# RPi_RFM12B_ISP.net
KiCad netlist of a schematic drawn in EAGLE
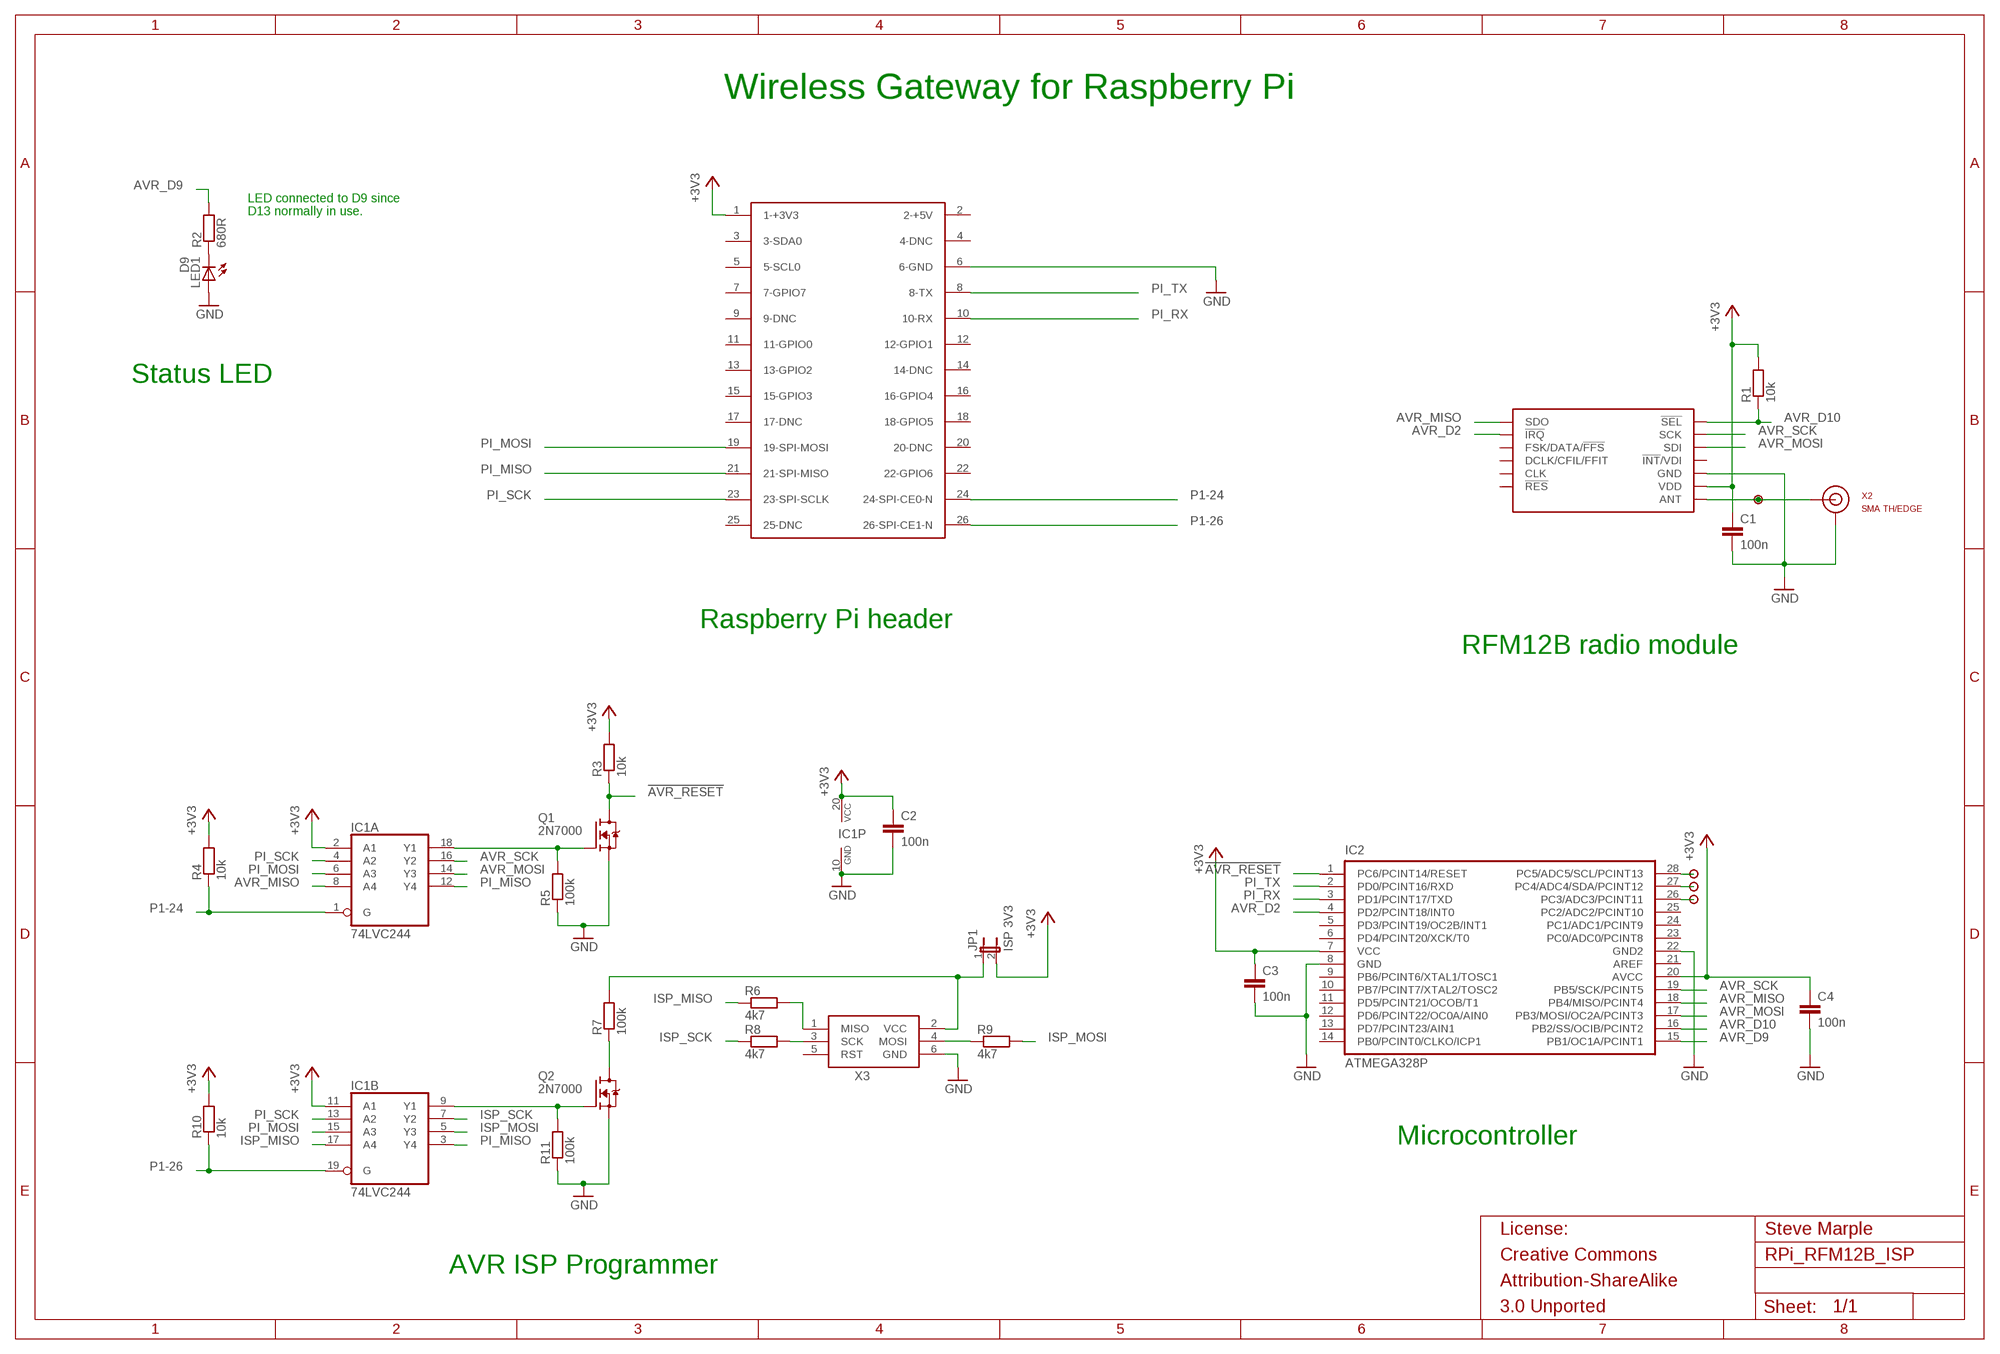
[diagram p0: schematic, sheet 1]

(export (version "E")
  (design (tool "Eeschema 10.0.6"))
  (components
    (comp (ref "AVR_A1")
      (value "PAD")
      (footprint "eagle-import:PAD")
      (libsource (lib "eagle-import") (part "PAD"))
    )
    (comp (ref "AVR_A2")
      (value "PAD")
      (footprint "eagle-import:PAD")
      (libsource (lib "eagle-import") (part "PAD"))
    )
    (comp (ref "AVR_A3")
      (value "PAD")
      (footprint "eagle-import:PAD")
      (libsource (lib "eagle-import") (part "PAD"))
    )
    (comp (ref "C1")
      (value "100n")
      (footprint "eagle-import:CAP-PTH-SMALL")
      (libsource (lib "eagle-import") (part "CAPPTH"))
    )
    (comp (ref "C2")
      (value "100n")
      (footprint "eagle-import:CAP-PTH-SMALL")
      (libsource (lib "eagle-import") (part "CAPPTH"))
    )
    (comp (ref "C3")
      (value "100n")
      (footprint "eagle-import:CAP-PTH-SMALL")
      (libsource (lib "eagle-import") (part "CAPPTH"))
    )
    (comp (ref "C4")
      (value "100n")
      (footprint "eagle-import:CAP-PTH-SMALL")
      (libsource (lib "eagle-import") (part "CAPPTH"))
    )
    (comp (ref "IC1")
      (value "74LVC244")
      (footprint "eagle-import:DIL20")
      (libsource (lib "eagle-import") (part "74244NHC"))
    )
    (comp (ref "IC2")
      (value "ATMEGA328P")
      (footprint "eagle-import:DIL28-N")
      (libsource (lib "eagle-import") (part "IC_UC_ATMEGA328PDIL"))
    )
    (comp (ref "JP1")
      (value "ISP 3V3")
      (footprint "eagle-import:1X02")
      (libsource (lib "eagle-import") (part "JUMPER-2PTH"))
    )
    (comp (ref "LED1")
      (value "D9")
      (footprint "eagle-import:LED3MM")
      (libsource (lib "eagle-import") (part "LED3MM"))
    )
    (comp (ref "Q1")
      (value "2N7000")
      (footprint "eagle-import:TO-92")
      (libsource (lib "eagle-import") (part "2N7000"))
    )
    (comp (ref "Q2")
      (value "2N7000")
      (footprint "eagle-import:TO-92")
      (libsource (lib "eagle-import") (part "2N7000"))
    )
    (comp (ref "R1")
      (value "10k")
      (footprint "eagle-import:RES-AXIAL-0.4")
      (libsource (lib "eagle-import") (part "RESISTOR"))
    )
    (comp (ref "R2")
      (value "680R")
      (footprint "eagle-import:RES-AXIAL-0.4")
      (libsource (lib "eagle-import") (part "RESISTOR"))
    )
    (comp (ref "R3")
      (value "10k")
      (footprint "eagle-import:RES-AXIAL-0.4")
      (libsource (lib "eagle-import") (part "RESISTOR"))
    )
    (comp (ref "R4")
      (value "10k")
      (footprint "eagle-import:RES-AXIAL-0.4")
      (libsource (lib "eagle-import") (part "RESISTOR"))
    )
    (comp (ref "R5")
      (value "100k")
      (footprint "eagle-import:RES-AXIAL-0.4")
      (libsource (lib "eagle-import") (part "RESISTOR"))
    )
    (comp (ref "R6")
      (value "4k7")
      (footprint "eagle-import:RES-AXIAL-0.4")
      (libsource (lib "eagle-import") (part "RESISTOR"))
    )
    (comp (ref "R7")
      (value "100k")
      (footprint "eagle-import:RES-AXIAL-0.4")
      (libsource (lib "eagle-import") (part "RESISTOR"))
    )
    (comp (ref "R8")
      (value "4k7")
      (footprint "eagle-import:RES-AXIAL-0.4")
      (libsource (lib "eagle-import") (part "RESISTOR"))
    )
    (comp (ref "R9")
      (value "4k7")
      (footprint "eagle-import:RES-AXIAL-0.4")
      (libsource (lib "eagle-import") (part "RESISTOR"))
    )
    (comp (ref "R10")
      (value "10k")
      (footprint "eagle-import:RES-AXIAL-0.4")
      (libsource (lib "eagle-import") (part "RESISTOR"))
    )
    (comp (ref "R11")
      (value "100k")
      (footprint "eagle-import:RES-AXIAL-0.4")
      (libsource (lib "eagle-import") (part "RESISTOR"))
    )
    (comp (ref "RF1")
      (value "RFM12B")
      (footprint "eagle-import:RFM12B")
      (libsource (lib "eagle-import") (part "RFM12BSMD"))
    )
    (comp (ref "RFM12B_ANT")
      (value "PAD")
      (footprint "eagle-import:PAD")
      (libsource (lib "eagle-import") (part "PAD"))
    )
    (comp (ref "X1")
      (value "P1A")
      (footprint "eagle-import:RASPBERRY-PI-HEADER")
      (libsource (lib "eagle-import") (part "RASPBERRY-PIHEADER"))
    )
    (comp (ref "X2")
      (value "SMA TH/EDGE")
      (footprint "eagle-import:SMA-THD-EDGE")
      (libsource (lib "eagle-import") (part "CONN-SMATHD-SMD-EDGE"))
    )
    (comp (ref "X3")
      (value "AVR ISP")
      (footprint "eagle-import:CONN-HARTING-ML6")
      (libsource (lib "eagle-import") (part "AVRISP-HEADER-6-SHROUDED"))
    )
  )
  (nets
    (net (code "1") (name "+3V3") (class "Default")
      (node (ref "C1") (pin "1") (pinfunction "1_1") (pintype "passive"))
      (node (ref "C2") (pin "1") (pinfunction "1_1") (pintype "passive"))
      (node (ref "C3") (pin "1") (pinfunction "1_1") (pintype "passive"))
      (node (ref "C4") (pin "1") (pinfunction "1_1") (pintype "passive"))
      (node (ref "IC1") (pin "11") (pinfunction "A1_11") (pintype "input"))
      (node (ref "IC1") (pin "2") (pinfunction "A1_2") (pintype "input"))
      (node (ref "IC1") (pin "20") (pinfunction "VCC_20") (pintype "power_in"))
      (node (ref "IC2") (pin "20") (pinfunction "AVCC_20") (pintype "bidirectional"))
      (node (ref "IC2") (pin "7") (pinfunction "VCC_7") (pintype "bidirectional"))
      (node (ref "JP1") (pin "2") (pinfunction "2_2") (pintype "passive"))
      (node (ref "R1") (pin "P$2") (pinfunction "2_P$2") (pintype "passive"))
      (node (ref "R10") (pin "P$2") (pinfunction "2_P$2") (pintype "passive"))
      (node (ref "R3") (pin "P$2") (pinfunction "2_P$2") (pintype "passive"))
      (node (ref "R4") (pin "P$2") (pinfunction "2_P$2") (pintype "passive"))
      (node (ref "RF1") (pin "VDD") (pinfunction "VDD_VDD") (pintype "power_in"))
      (node (ref "X1") (pin "1") (pinfunction "1-+3V3_1") (pintype "bidirectional"))
    )
    (net (code "2") (name "/AVR_D2") (class "Default")
      (node (ref "IC2") (pin "4") (pinfunction "PD2/PCINT18/INT0_4") (pintype "bidirectional"))
      (node (ref "RF1") (pin "!IRQ") (pinfunction "~{IRQ}_!IRQ") (pintype "output"))
    )
    (net (code "3") (name "/AVR_D9") (class "Default")
      (node (ref "IC2") (pin "15") (pinfunction "PB1/OC1A/PCINT1_15") (pintype "bidirectional"))
      (node (ref "R2") (pin "P$2") (pinfunction "2_P$2") (pintype "passive"))
    )
    (net (code "4") (name "/AVR_D10") (class "Default")
      (node (ref "IC2") (pin "16") (pinfunction "PB2/SS/OCIB/PCINT2_16") (pintype "bidirectional"))
      (node (ref "R1") (pin "P$1") (pinfunction "1_P$1") (pintype "passive"))
      (node (ref "RF1") (pin "!SEL") (pinfunction "~{SEL}_!SEL") (pintype "input"))
    )
    (net (code "5") (name "/AVR_MISO") (class "Default")
      (node (ref "IC1") (pin "8") (pinfunction "A4_8") (pintype "input"))
      (node (ref "IC2") (pin "18") (pinfunction "PB4/MISO/PCINT4_18") (pintype "bidirectional"))
      (node (ref "RF1") (pin "SDO") (pinfunction "SDO_SDO") (pintype "output"))
    )
    (net (code "6") (name "/AVR_MOSI") (class "Default")
      (node (ref "IC1") (pin "14") (pinfunction "Y3_14") (pintype "tri_state"))
      (node (ref "IC2") (pin "17") (pinfunction "PB3/MOSI/OC2A/PCINT3_17") (pintype "bidirectional"))
      (node (ref "RF1") (pin "SDI") (pinfunction "SDI_SDI") (pintype "input"))
    )
    (net (code "7") (name "/AVR_SCK") (class "Default")
      (node (ref "IC1") (pin "16") (pinfunction "Y2_16") (pintype "tri_state"))
      (node (ref "IC2") (pin "19") (pinfunction "PB5/SCK/PCINT5_19") (pintype "bidirectional"))
      (node (ref "RF1") (pin "SCK") (pinfunction "SCK_SCK") (pintype "input"))
    )
    (net (code "8") (name "/ISP_MISO") (class "Default")
      (node (ref "IC1") (pin "17") (pinfunction "A4_17") (pintype "input"))
      (node (ref "R6") (pin "P$1") (pinfunction "1_P$1") (pintype "passive"))
    )
    (net (code "9") (name "/ISP_MOSI") (class "Default")
      (node (ref "IC1") (pin "5") (pinfunction "Y3_5") (pintype "tri_state"))
      (node (ref "R9") (pin "P$2") (pinfunction "2_P$2") (pintype "passive"))
    )
    (net (code "10") (name "/ISP_SCK") (class "Default")
      (node (ref "IC1") (pin "7") (pinfunction "Y2_7") (pintype "tri_state"))
      (node (ref "R8") (pin "P$1") (pinfunction "1_P$1") (pintype "passive"))
    )
    (net (code "11") (name "/P1-24") (class "Default")
      (node (ref "IC1") (pin "1") (pinfunction "G_1") (pintype "input"))
      (node (ref "R4") (pin "P$1") (pinfunction "1_P$1") (pintype "passive"))
      (node (ref "X1") (pin "24") (pinfunction "24-SPI-CE0-N_24") (pintype "bidirectional"))
    )
    (net (code "12") (name "/P1-26") (class "Default")
      (node (ref "IC1") (pin "19") (pinfunction "G_19") (pintype "input"))
      (node (ref "R10") (pin "P$1") (pinfunction "1_P$1") (pintype "passive"))
      (node (ref "X1") (pin "26") (pinfunction "26-SPI-CE1-N_26") (pintype "bidirectional"))
    )
    (net (code "13") (name "/PI_MISO") (class "Default")
      (node (ref "IC1") (pin "12") (pinfunction "Y4_12") (pintype "tri_state"))
      (node (ref "IC1") (pin "3") (pinfunction "Y4_3") (pintype "tri_state"))
      (node (ref "X1") (pin "21") (pinfunction "21-SPI-MISO_21") (pintype "bidirectional"))
    )
    (net (code "14") (name "/PI_MOSI") (class "Default")
      (node (ref "IC1") (pin "15") (pinfunction "A3_15") (pintype "input"))
      (node (ref "IC1") (pin "6") (pinfunction "A3_6") (pintype "input"))
      (node (ref "X1") (pin "19") (pinfunction "19-SPI-MOSI_19") (pintype "bidirectional"))
    )
    (net (code "15") (name "/PI_RX") (class "Default")
      (node (ref "IC2") (pin "3") (pinfunction "PD1/PCINT17/TXD_3") (pintype "bidirectional"))
      (node (ref "X1") (pin "10") (pinfunction "10-RX_10") (pintype "bidirectional"))
    )
    (net (code "16") (name "/PI_SCK") (class "Default")
      (node (ref "IC1") (pin "13") (pinfunction "A2_13") (pintype "input"))
      (node (ref "IC1") (pin "4") (pinfunction "A2_4") (pintype "input"))
      (node (ref "X1") (pin "23") (pinfunction "23-SPI-SCLK_23") (pintype "bidirectional"))
    )
    (net (code "17") (name "/PI_TX") (class "Default")
      (node (ref "IC2") (pin "2") (pinfunction "PD0/PCINT16/RXD_2") (pintype "bidirectional"))
      (node (ref "X1") (pin "8") (pinfunction "8-TX_8") (pintype "bidirectional"))
    )
    (net (code "18") (name "/~{AVR_RESET}") (class "Default")
      (node (ref "IC2") (pin "1") (pinfunction "PC6/PCINT14/RESET_1") (pintype "bidirectional"))
      (node (ref "Q1") (pin "3") (pinfunction "D_3") (pintype "passive"))
      (node (ref "R3") (pin "P$1") (pinfunction "1_P$1") (pintype "passive"))
    )
    (net (code "19") (name "GND") (class "Default")
      (node (ref "C1") (pin "2") (pinfunction "2_2") (pintype "passive"))
      (node (ref "C2") (pin "2") (pinfunction "2_2") (pintype "passive"))
      (node (ref "C3") (pin "2") (pinfunction "2_2") (pintype "passive"))
      (node (ref "C4") (pin "2") (pinfunction "2_2") (pintype "passive"))
      (node (ref "IC1") (pin "10") (pinfunction "GND_10") (pintype "power_in"))
      (node (ref "IC2") (pin "22") (pinfunction "GND2_22") (pintype "bidirectional"))
      (node (ref "IC2") (pin "8") (pinfunction "GND_8") (pintype "bidirectional"))
      (node (ref "LED1") (pin "A") (pinfunction "A_A") (pintype "passive"))
      (node (ref "Q1") (pin "1") (pinfunction "S_1") (pintype "passive"))
      (node (ref "Q2") (pin "1") (pinfunction "S_1") (pintype "passive"))
      (node (ref "R11") (pin "P$1") (pinfunction "1_P$1") (pintype "passive"))
      (node (ref "R5") (pin "P$1") (pinfunction "1_P$1") (pintype "passive"))
      (node (ref "RF1") (pin "GND@0") (pinfunction "GND_GND@0") (pintype "power_in"))
      (node (ref "RF1") (pin "GND@1") (pinfunction "GND_GND@1") (pintype "power_in"))
      (node (ref "X1") (pin "6") (pinfunction "6-GND_6") (pintype "bidirectional"))
      (node (ref "X2") (pin "GND@0") (pinfunction "GND_GND@0") (pintype "bidirectional"))
      (node (ref "X2") (pin "GND@1") (pinfunction "GND_GND@1") (pintype "bidirectional"))
      (node (ref "X2") (pin "GND@2") (pinfunction "GND_GND@2") (pintype "bidirectional"))
      (node (ref "X2") (pin "GND@3") (pinfunction "GND_GND@3") (pintype "bidirectional"))
      (node (ref "X2") (pin "GND@EDGE0") (pinfunction "GND_GND@EDGE0") (pintype "bidirectional"))
      (node (ref "X2") (pin "GND@EDGE1") (pinfunction "GND_GND@EDGE1") (pintype "bidirectional"))
      (node (ref "X2") (pin "GND@EDGE2") (pinfunction "GND_GND@EDGE2") (pintype "bidirectional"))
      (node (ref "X2") (pin "GND@EDGE3") (pinfunction "GND_GND@EDGE3") (pintype "bidirectional"))
      (node (ref "X3") (pin "6") (pinfunction "GND_6") (pintype "power_in"))
    )
    (net (code "20") (name "Net-(IC1A-Y1)") (class "Default")
      (node (ref "IC1") (pin "18") (pinfunction "Y1_18") (pintype "tri_state"))
      (node (ref "Q1") (pin "2") (pinfunction "G_2") (pintype "passive"))
      (node (ref "R5") (pin "P$2") (pinfunction "2_P$2") (pintype "passive"))
    )
    (net (code "21") (name "Net-(IC1B-Y1)") (class "Default")
      (node (ref "IC1") (pin "9") (pinfunction "Y1_9") (pintype "tri_state"))
      (node (ref "Q2") (pin "2") (pinfunction "G_2") (pintype "passive"))
      (node (ref "R11") (pin "P$2") (pinfunction "2_P$2") (pintype "passive"))
    )
    (net (code "22") (name "Net-(IC2-PC3{slash}ADC3{slash}PCINT11)") (class "Default")
      (node (ref "AVR_A3") (pin "1") (pinfunction "1_1") (pintype "bidirectional"))
      (node (ref "IC2") (pin "26") (pinfunction "PC3/ADC3/PCINT11_26") (pintype "bidirectional"))
    )
    (net (code "23") (name "Net-(IC2-PC4{slash}ADC4{slash}SDA{slash}PCINT12)") (class "Default")
      (node (ref "AVR_A2") (pin "1") (pinfunction "1_1") (pintype "bidirectional"))
      (node (ref "IC2") (pin "27") (pinfunction "PC4/ADC4/SDA/PCINT12_27") (pintype "bidirectional"))
    )
    (net (code "24") (name "Net-(IC2-PC5{slash}ADC5{slash}SCL{slash}PCINT13)") (class "Default")
      (node (ref "AVR_A1") (pin "1") (pinfunction "1_1") (pintype "bidirectional"))
      (node (ref "IC2") (pin "28") (pinfunction "PC5/ADC5/SCL/PCINT13_28") (pintype "bidirectional"))
    )
    (net (code "25") (name "Net-(LED1-C)") (class "Default")
      (node (ref "LED1") (pin "K") (pinfunction "C_K") (pintype "passive"))
      (node (ref "R2") (pin "P$1") (pinfunction "1_P$1") (pintype "passive"))
    )
    (net (code "26") (name "Net-(Q2-D)") (class "Default")
      (node (ref "Q2") (pin "3") (pinfunction "D_3") (pintype "passive"))
      (node (ref "R7") (pin "P$1") (pinfunction "1_P$1") (pintype "passive"))
    )
    (net (code "27") (name "Net-(R6-2)") (class "Default")
      (node (ref "R6") (pin "P$2") (pinfunction "2_P$2") (pintype "passive"))
      (node (ref "X3") (pin "1") (pinfunction "MISO_1") (pintype "input"))
    )
    (net (code "28") (name "Net-(R7-2)") (class "Default")
      (node (ref "JP1") (pin "1") (pinfunction "1_1") (pintype "passive"))
      (node (ref "R7") (pin "P$2") (pinfunction "2_P$2") (pintype "passive"))
      (node (ref "X3") (pin "2") (pinfunction "VCC_2") (pintype "power_in"))
    )
    (net (code "29") (name "Net-(R8-2)") (class "Default")
      (node (ref "R8") (pin "P$2") (pinfunction "2_P$2") (pintype "passive"))
      (node (ref "X3") (pin "3") (pinfunction "SCK_3") (pintype "output"))
    )
    (net (code "30") (name "Net-(R9-1)") (class "Default")
      (node (ref "R9") (pin "P$1") (pinfunction "1_P$1") (pintype "passive"))
      (node (ref "X3") (pin "4") (pinfunction "MOSI_4") (pintype "output"))
    )
    (net (code "31") (name "Net-(RF1-PadANT)") (class "Default")
      (node (ref "RF1") (pin "ANT") (pinfunction "ANT_ANT") (pintype "passive"))
      (node (ref "RFM12B_ANT") (pin "1") (pinfunction "1_1") (pintype "bidirectional"))
      (node (ref "X2") (pin "SIG") (pinfunction "SIGNAL_SIG") (pintype "bidirectional"))
      (node (ref "X2") (pin "SIG@EDGE") (pinfunction "SIGNAL_SIG@EDGE") (pintype "bidirectional"))
    )
    (net (code "32") (name "unconnected-(IC2-AREF-Pad21)") (class "Default")
      (node (ref "IC2") (pin "21") (pinfunction "AREF_21") (pintype "bidirectional"))
    )
    (net (code "33") (name "unconnected-(IC2-PB0{slash}PCINT0{slash}CLKO{slash}ICP1-Pad14)") (class "Default")
      (node (ref "IC2") (pin "14") (pinfunction "PB0/PCINT0/CLKO/ICP1_14") (pintype "bidirectional"))
    )
    (net (code "34") (name "unconnected-(IC2-PB6{slash}PCINT6{slash}XTAL1{slash}TOSC1-Pad9)") (class "Default")
      (node (ref "IC2") (pin "9") (pinfunction "PB6/PCINT6/XTAL1/TOSC1_9") (pintype "bidirectional"))
    )
    (net (code "35") (name "unconnected-(IC2-PB7{slash}PCINT7{slash}XTAL2{slash}TOSC2-Pad10)") (class "Default")
      (node (ref "IC2") (pin "10") (pinfunction "PB7/PCINT7/XTAL2/TOSC2_10") (pintype "bidirectional"))
    )
    (net (code "36") (name "unconnected-(IC2-PC0{slash}ADC0{slash}PCINT8-Pad23)") (class "Default")
      (node (ref "IC2") (pin "23") (pinfunction "PC0/ADC0/PCINT8_23") (pintype "bidirectional"))
    )
    (net (code "37") (name "unconnected-(IC2-PC1{slash}ADC1{slash}PCINT9-Pad24)") (class "Default")
      (node (ref "IC2") (pin "24") (pinfunction "PC1/ADC1/PCINT9_24") (pintype "bidirectional"))
    )
    (net (code "38") (name "unconnected-(IC2-PC2{slash}ADC2{slash}PCINT10-Pad25)") (class "Default")
      (node (ref "IC2") (pin "25") (pinfunction "PC2/ADC2/PCINT10_25") (pintype "bidirectional"))
    )
    (net (code "39") (name "unconnected-(IC2-PD3{slash}PCINT19{slash}OC2B{slash}INT1-Pad5)") (class "Default")
      (node (ref "IC2") (pin "5") (pinfunction "PD3/PCINT19/OC2B/INT1_5") (pintype "bidirectional"))
    )
    (net (code "40") (name "unconnected-(IC2-PD4{slash}PCINT20{slash}XCK{slash}T0-Pad6)") (class "Default")
      (node (ref "IC2") (pin "6") (pinfunction "PD4/PCINT20/XCK/T0_6") (pintype "bidirectional"))
    )
    (net (code "41") (name "unconnected-(IC2-PD5{slash}PCINT21{slash}OCOB{slash}T1-Pad11)") (class "Default")
      (node (ref "IC2") (pin "11") (pinfunction "PD5/PCINT21/OCOB/T1_11") (pintype "bidirectional"))
    )
    (net (code "42") (name "unconnected-(IC2-PD6{slash}PCINT22{slash}OC0A{slash}AIN0-Pad12)") (class "Default")
      (node (ref "IC2") (pin "12") (pinfunction "PD6/PCINT22/OC0A/AIN0_12") (pintype "bidirectional"))
    )
    (net (code "43") (name "unconnected-(IC2-PD7{slash}PCINT23{slash}AIN1-Pad13)") (class "Default")
      (node (ref "IC2") (pin "13") (pinfunction "PD7/PCINT23/AIN1_13") (pintype "bidirectional"))
    )
    (net (code "44") (name "unconnected-(RF1-FSK{slash}DATA{slash}~{FFS}-PadFSK{slash}DATA{slash}!FFS)") (class "Default")
      (node (ref "RF1") (pin "FSK/DATA/!FFS") (pinfunction "FSK/DATA/~{FFS}_FSK/DATA/!FFS") (pintype "bidirectional"))
    )
    (net (code "45") (name "unconnected-(RF1-PadCLK)") (class "Default")
      (node (ref "RF1") (pin "CLK") (pinfunction "CLK_CLK") (pintype "output"))
    )
    (net (code "46") (name "unconnected-(RF1-PadDCLK{slash}CFIL{slash}FFIT)") (class "Default")
      (node (ref "RF1") (pin "DCLK/CFIL/FFIT") (pinfunction "DCLK/CFIL/FFIT_DCLK/CFIL/FFIT") (pintype "bidirectional"))
    )
    (net (code "47") (name "unconnected-(RF1-~{INT}{slash}VDI-Pad!INT!{slash}VDI)") (class "Default")
      (node (ref "RF1") (pin "!INT!/VDI") (pinfunction "~{INT}/VDI_!INT!/VDI") (pintype "bidirectional"))
    )
    (net (code "48") (name "unconnected-(RF1-~{RES}-Pad!RES)") (class "Default")
      (node (ref "RF1") (pin "!RES") (pinfunction "~{RES}_!RES") (pintype "bidirectional"))
    )
    (net (code "49") (name "unconnected-(X1-2-+5V-Pad2)") (class "Default")
      (node (ref "X1") (pin "2") (pinfunction "2-+5V_2") (pintype "bidirectional"))
    )
    (net (code "50") (name "unconnected-(X1-3-SDA0-Pad3)") (class "Default")
      (node (ref "X1") (pin "3") (pinfunction "3-SDA0_3") (pintype "bidirectional"))
    )
    (net (code "51") (name "unconnected-(X1-4-DNC-Pad4)") (class "Default")
      (node (ref "X1") (pin "4") (pinfunction "4-DNC_4") (pintype "bidirectional"))
    )
    (net (code "52") (name "unconnected-(X1-5-SCL0-Pad5)") (class "Default")
      (node (ref "X1") (pin "5") (pinfunction "5-SCL0_5") (pintype "bidirectional"))
    )
    (net (code "53") (name "unconnected-(X1-7-GPIO7-Pad7)") (class "Default")
      (node (ref "X1") (pin "7") (pinfunction "7-GPIO7_7") (pintype "bidirectional"))
    )
    (net (code "54") (name "unconnected-(X1-9-DNC-Pad9)") (class "Default")
      (node (ref "X1") (pin "9") (pinfunction "9-DNC_9") (pintype "bidirectional"))
    )
    (net (code "55") (name "unconnected-(X1-11-GPIO0-Pad11)") (class "Default")
      (node (ref "X1") (pin "11") (pinfunction "11-GPIO0_11") (pintype "bidirectional"))
    )
    (net (code "56") (name "unconnected-(X1-12-GPIO1-Pad12)") (class "Default")
      (node (ref "X1") (pin "12") (pinfunction "12-GPIO1_12") (pintype "bidirectional"))
    )
    (net (code "57") (name "unconnected-(X1-13-GPIO2-Pad13)") (class "Default")
      (node (ref "X1") (pin "13") (pinfunction "13-GPIO2_13") (pintype "bidirectional"))
    )
    (net (code "58") (name "unconnected-(X1-14-DNC-Pad14)") (class "Default")
      (node (ref "X1") (pin "14") (pinfunction "14-DNC_14") (pintype "bidirectional"))
    )
    (net (code "59") (name "unconnected-(X1-15-GPIO3-Pad15)") (class "Default")
      (node (ref "X1") (pin "15") (pinfunction "15-GPIO3_15") (pintype "bidirectional"))
    )
    (net (code "60") (name "unconnected-(X1-16-GPIO4-Pad16)") (class "Default")
      (node (ref "X1") (pin "16") (pinfunction "16-GPIO4_16") (pintype "bidirectional"))
    )
    (net (code "61") (name "unconnected-(X1-17-DNC-Pad17)") (class "Default")
      (node (ref "X1") (pin "17") (pinfunction "17-DNC_17") (pintype "bidirectional"))
    )
    (net (code "62") (name "unconnected-(X1-18-GPIO5-Pad18)") (class "Default")
      (node (ref "X1") (pin "18") (pinfunction "18-GPIO5_18") (pintype "bidirectional"))
    )
    (net (code "63") (name "unconnected-(X1-20-DNC-Pad20)") (class "Default")
      (node (ref "X1") (pin "20") (pinfunction "20-DNC_20") (pintype "bidirectional"))
    )
    (net (code "64") (name "unconnected-(X1-22-GPIO6-Pad22)") (class "Default")
      (node (ref "X1") (pin "22") (pinfunction "22-GPIO6_22") (pintype "bidirectional"))
    )
    (net (code "65") (name "unconnected-(X1-25-DNC-Pad25)") (class "Default")
      (node (ref "X1") (pin "25") (pinfunction "25-DNC_25") (pintype "bidirectional"))
    )
    (net (code "66") (name "unconnected-(X3-RST-Pad5)") (class "Default")
      (node (ref "X3") (pin "5") (pinfunction "RST_5") (pintype "output"))
    )
  )
)
